# Audio.net
KiCad netlist of a schematic drawn in Altium Designer
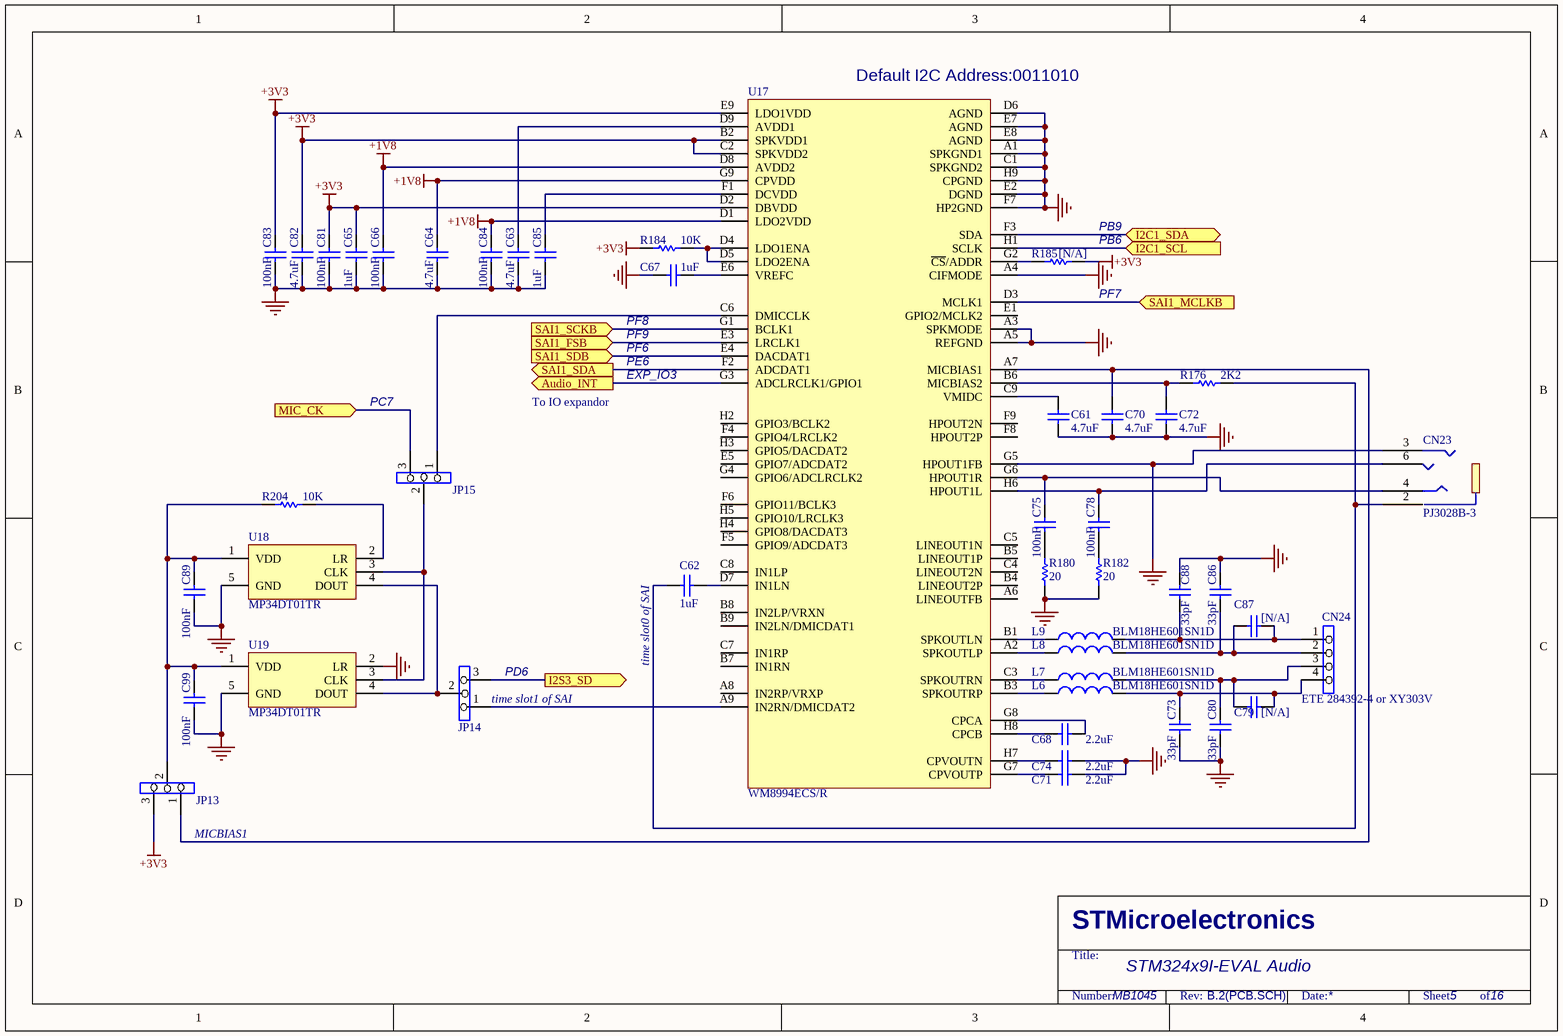
[diagram p0: Audio.SchDoc]

(export (version "E")
  (design (tool "Eeschema 10.0.6"))
  (components
    (comp (ref "C61")
      (value "4.7uF")
      (footprint "0603C")
      (description "Capacitor")
      (fields (field (name "PUBLISHER") "Altium Limited"))
      (libsource (lib "Miscellaneous Devices") (part "Cap"))
    )
    (comp (ref "C62")
      (value "1uF")
      (footprint "0603C")
      (description "Capacitor")
      (fields (field (name "PUBLISHER") "Altium Limited"))
      (libsource (lib "Miscellaneous Devices") (part "CAP"))
    )
    (comp (ref "C63")
      (value "4.7uF")
      (footprint "0603C")
      (description "Capacitor")
      (fields (field (name "PUBLISHER") "Altium Limited"))
      (libsource (lib "Miscellaneous Devices") (part "Cap"))
    )
    (comp (ref "C64")
      (value "4.7uF")
      (footprint "0603C")
      (description "Capacitor")
      (fields (field (name "PUBLISHER") "Altium Limited"))
      (libsource (lib "Miscellaneous Devices") (part "Cap"))
    )
    (comp (ref "C65")
      (value "1uF")
      (footprint "0603C")
      (description "Capacitor")
      (fields (field (name "PUBLISHER") "Altium Limited"))
      (libsource (lib "Miscellaneous Devices") (part "CAP"))
    )
    (comp (ref "C66")
      (value "100nF")
      (footprint "0603C")
      (description "Capacitor")
      (fields (field (name "PUBLISHER") "Altium Limited"))
      (libsource (lib "Miscellaneous Devices") (part "Cap"))
    )
    (comp (ref "C67")
      (value "1uF")
      (footprint "0603C")
      (description "Capacitor")
      (fields (field (name "PUBLISHER") "Altium Limited"))
      (libsource (lib "Miscellaneous Devices") (part "CAP"))
    )
    (comp (ref "C68")
      (value "2.2uF")
      (footprint "0603C")
      (description "Capacitor")
      (fields (field (name "PUBLISHER") "Altium Limited"))
      (libsource (lib "Miscellaneous Devices") (part "CAP"))
    )
    (comp (ref "C70")
      (value "4.7uF")
      (footprint "0603C")
      (description "Capacitor")
      (fields (field (name "PUBLISHER") "Altium Limited"))
      (libsource (lib "Miscellaneous Devices") (part "Cap"))
    )
    (comp (ref "C71")
      (value "2.2uF")
      (footprint "0603C")
      (description "Capacitor")
      (fields (field (name "PUBLISHER") "Altium Limited"))
      (libsource (lib "Miscellaneous Devices") (part "CAP"))
    )
    (comp (ref "C72")
      (value "4.7uF")
      (footprint "0603C")
      (description "Capacitor")
      (fields (field (name "PUBLISHER") "Altium Limited"))
      (libsource (lib "Miscellaneous Devices") (part "Cap"))
    )
    (comp (ref "C73")
      (value "33pF")
      (footprint "0603C")
      (description "Capacitor")
      (fields (field (name "PUBLISHER") "Altium Limited"))
      (libsource (lib "Miscellaneous Devices") (part "Cap"))
    )
    (comp (ref "C74")
      (value "2.2uF")
      (footprint "0603C")
      (description "Capacitor")
      (fields (field (name "PUBLISHER") "Altium Limited"))
      (libsource (lib "Miscellaneous Devices") (part "CAP"))
    )
    (comp (ref "C75")
      (value "100nF")
      (footprint "0603C")
      (description "Capacitor")
      (fields (field (name "PUBLISHER") "Altium Limited"))
      (libsource (lib "Miscellaneous Devices") (part "Cap"))
    )
    (comp (ref "C78")
      (value "100nF")
      (footprint "0603C")
      (description "Capacitor")
      (fields (field (name "PUBLISHER") "Altium Limited"))
      (libsource (lib "Miscellaneous Devices") (part "Cap"))
    )
    (comp (ref "C79")
      (value "[N/A]")
      (footprint "0603C")
      (description "Capacitor")
      (fields (field (name "PUBLISHER") "Altium Limited"))
      (libsource (lib "Miscellaneous Devices") (part "Cap"))
    )
    (comp (ref "C80")
      (value "33pF")
      (footprint "0603C")
      (description "Capacitor")
      (fields (field (name "PUBLISHER") "Altium Limited"))
      (libsource (lib "Miscellaneous Devices") (part "Cap"))
    )
    (comp (ref "C81")
      (value "100nF")
      (footprint "0603C")
      (description "Capacitor")
      (fields (field (name "PUBLISHER") "Altium Limited"))
      (libsource (lib "Miscellaneous Devices") (part "Cap"))
    )
    (comp (ref "C82")
      (value "4.7uF")
      (footprint "0603C")
      (description "Capacitor")
      (fields (field (name "PUBLISHER") "Altium Limited"))
      (libsource (lib "Miscellaneous Devices") (part "Cap"))
    )
    (comp (ref "C83")
      (value "100nF")
      (footprint "0603C")
      (description "Capacitor")
      (fields (field (name "PUBLISHER") "Altium Limited"))
      (libsource (lib "Miscellaneous Devices") (part "Cap"))
    )
    (comp (ref "C84")
      (value "100nF")
      (footprint "0603C")
      (description "Capacitor")
      (fields (field (name "PUBLISHER") "Altium Limited"))
      (libsource (lib "Miscellaneous Devices") (part "Cap"))
    )
    (comp (ref "C85")
      (value "1uF")
      (footprint "0603C")
      (description "Capacitor")
      (fields (field (name "PUBLISHER") "Altium Limited"))
      (libsource (lib "Miscellaneous Devices") (part "CAP"))
    )
    (comp (ref "C86")
      (value "33pF")
      (footprint "0603C")
      (description "Capacitor")
      (fields (field (name "PUBLISHER") "Altium Limited"))
      (libsource (lib "Miscellaneous Devices") (part "Cap"))
    )
    (comp (ref "C87")
      (value "[N/A]")
      (footprint "0603C")
      (description "Capacitor")
      (fields (field (name "PUBLISHER") "Altium Limited"))
      (libsource (lib "Miscellaneous Devices") (part "Cap"))
    )
    (comp (ref "C88")
      (value "33pF")
      (footprint "0603C")
      (description "Capacitor")
      (fields (field (name "PUBLISHER") "Altium Limited"))
      (libsource (lib "Miscellaneous Devices") (part "Cap"))
    )
    (comp (ref "C89")
      (value "100nF")
      (footprint "0603C")
      (description "Capacitor")
      (fields (field (name "PUBLISHER") "Altium Limited"))
      (libsource (lib "Miscellaneous Devices") (part "Cap"))
    )
    (comp (ref "C99")
      (value "100nF")
      (footprint "0603C")
      (description "Capacitor")
      (fields (field (name "PUBLISHER") "Altium Limited"))
      (libsource (lib "Miscellaneous Devices") (part "Cap"))
    )
    (comp (ref "CN23") (value "PJ3028B-3") (footprint "PJ3028B") (libsource (lib "MB786") (part "PJ3028B-3")))
    (comp (ref "CN24")
      (value "ETE 284392-4 or XY303V")
      (footprint "BUCHANAN_284392-4")
      (description "ETE 284392-4")
      (libsource (lib "mb1045") (part "ETE 284392-4 or XY303V"))
    )
    (comp (ref "JP13") (value "~") (footprint "SIP3") (libsource (lib "STR910_SCHLIB") (part "Jumper3")))
    (comp (ref "JP14") (value "~") (footprint "SIP3") (libsource (lib "STR910_SCHLIB") (part "Jumper3")))
    (comp (ref "JP15") (value "~") (footprint "SIP3") (libsource (lib "STR910_SCHLIB") (part "Jumper3")))
    (comp (ref "L6")
      (value "BLM18HE601SN1D")
      (footprint "0603L")
      (description "Inductor")
      (fields (field (name "PUBLISHER") "Altium Limited"))
      (libsource (lib "Miscellaneous Devices") (part "Inductor"))
    )
    (comp (ref "L7")
      (value "BLM18HE601SN1D")
      (footprint "0603L")
      (description "Inductor")
      (fields (field (name "PUBLISHER") "Altium Limited"))
      (libsource (lib "Miscellaneous Devices") (part "Inductor"))
    )
    (comp (ref "L8")
      (value "BLM18HE601SN1D")
      (footprint "0603L")
      (description "Inductor")
      (fields (field (name "PUBLISHER") "Altium Limited"))
      (libsource (lib "Miscellaneous Devices") (part "Inductor"))
    )
    (comp (ref "L9")
      (value "BLM18HE601SN1D")
      (footprint "0603L")
      (description "Inductor")
      (fields (field (name "PUBLISHER") "Altium Limited"))
      (libsource (lib "Miscellaneous Devices") (part "Inductor"))
    )
    (comp (ref "R176")
      (value "2K2")
      (footprint "0603R")
      (description "Resistor")
      (fields (field (name "PUBLISHER") "Altium Limited"))
      (libsource (lib "Miscellaneous Devices") (part "Res1"))
    )
    (comp (ref "R180")
      (value "20")
      (footprint "0603R")
      (description "Resistor")
      (fields (field (name "PUBLISHER") "Altium Limited"))
      (libsource (lib "Miscellaneous Devices") (part "Res1"))
    )
    (comp (ref "R182")
      (value "20")
      (footprint "0603R")
      (description "Resistor")
      (fields (field (name "PUBLISHER") "Altium Limited"))
      (libsource (lib "Miscellaneous Devices") (part "Res1"))
    )
    (comp (ref "R184")
      (value "10K")
      (footprint "0603R")
      (description "Resistor")
      (fields (field (name "PUBLISHER") "Altium Limited"))
      (libsource (lib "Miscellaneous Devices") (part "Res1"))
    )
    (comp (ref "R185")
      (value "[N/A]")
      (footprint "0603R")
      (description "Resistor")
      (fields (field (name "PUBLISHER") "Altium Limited"))
      (libsource (lib "Miscellaneous Devices") (part "Res1"))
    )
    (comp (ref "R204")
      (value "10K")
      (footprint "0603R")
      (description "Resistor")
      (fields (field (name "PUBLISHER") "Altium Limited"))
      (libsource (lib "Miscellaneous Devices") (part "Res1"))
    )
    (comp (ref "U17")
      (value "WM8994ECS/R")
      (footprint "BGA72_0R5_4R5X4")
      (libsource (lib "mb1045") (part "WM8994ECS/R"))
    )
    (comp (ref "U18")
      (value "MP34DT01TR")
      (footprint "MP34DT01TR")
      (description "MEMS audio sensor")
      (fields (field (name "PUBLISHER") "Altium Limited"))
      (libsource (lib "mb1045") (part "MP34DT01TR"))
    )
    (comp (ref "U19")
      (value "MP34DT01TR")
      (footprint "MP34DT01TR")
      (description "MEMS audio sensor")
      (fields (field (name "PUBLISHER") "Altium Limited"))
      (libsource (lib "mb1045") (part "MP34DT01TR"))
    )
  )
  (nets
    (net (code "1") (name "+1V8") (class "Default")
      (node (ref "C64") (pin "1") (pinfunction "1_1") (pintype "passive"))
      (node (ref "C66") (pin "1") (pinfunction "1_1") (pintype "passive"))
      (node (ref "C84") (pin "1") (pinfunction "1_1") (pintype "passive"))
      (node (ref "U17") (pin "D1") (pinfunction "LDO2VDD_D1") (pintype "passive"))
      (node (ref "U17") (pin "D8") (pinfunction "AVDD2_D8") (pintype "passive"))
      (node (ref "U17") (pin "G9") (pinfunction "CPVDD_G9") (pintype "passive"))
    )
    (net (code "2") (name "+3V3") (class "Default")
      (node (ref "C65") (pin "1") (pinfunction "1_1") (pintype "passive"))
      (node (ref "C81") (pin "1") (pinfunction "1_1") (pintype "passive"))
      (node (ref "C82") (pin "1") (pinfunction "1_1") (pintype "passive"))
      (node (ref "C83") (pin "1") (pinfunction "1_1") (pintype "passive"))
      (node (ref "JP13") (pin "3") (pintype "passive"))
      (node (ref "R184") (pin "2") (pinfunction "2_2") (pintype "passive"))
      (node (ref "R185") (pin "1") (pinfunction "1_1") (pintype "passive"))
      (node (ref "U17") (pin "B2") (pinfunction "SPKVDD1_B2") (pintype "passive"))
      (node (ref "U17") (pin "C2") (pinfunction "SPKVDD2_C2") (pintype "passive"))
      (node (ref "U17") (pin "D2") (pinfunction "DBVDD_D2") (pintype "passive"))
      (node (ref "U17") (pin "E9") (pinfunction "LDO1VDD_E9") (pintype "passive"))
    )
    (net (code "3") (name "/Audio_INT") (class "Default")
      (node (ref "U17") (pin "G3") (pinfunction "ADCLRCLK1/GPIO1_G3") (pintype "passive"))
    )
    (net (code "4") (name "/I2C1_SCL") (class "Default")
      (node (ref "U17") (pin "H1") (pinfunction "SCLK_H1") (pintype "passive"))
    )
    (net (code "5") (name "/I2C1_SDA") (class "Default")
      (node (ref "U17") (pin "F3") (pinfunction "SDA_F3") (pintype "passive"))
    )
    (net (code "6") (name "/I2S3_SD") (class "Default") (node (ref "JP14") (pin "3") (pintype "passive")))
    (net (code "7") (name "/MIC_CK") (class "Default") (node (ref "JP15") (pin "3") (pintype "passive")))
    (net (code "8") (name "/SAI1_FSB") (class "Default")
      (node (ref "U17") (pin "E3") (pinfunction "LRCLK1_E3") (pintype "passive"))
    )
    (net (code "9") (name "/SAI1_MCLKB") (class "Default")
      (node (ref "U17") (pin "D3") (pinfunction "MCLK1_D3") (pintype "passive"))
    )
    (net (code "10") (name "/SAI1_SCKB") (class "Default")
      (node (ref "U17") (pin "G1") (pinfunction "BCLK1_G1") (pintype "passive"))
    )
    (net (code "11") (name "/SAI1_SDA") (class "Default")
      (node (ref "U17") (pin "F2") (pinfunction "ADCDAT1_F2") (pintype "passive"))
    )
    (net (code "12") (name "/SAI1_SDB") (class "Default")
      (node (ref "U17") (pin "E4") (pinfunction "DACDAT1_E4") (pintype "passive"))
    )
    (net (code "13") (name "GND") (class "Default")
      (node (ref "C61") (pin "1") (pinfunction "1_1") (pintype "passive"))
      (node (ref "C63") (pin "2") (pinfunction "2_2") (pintype "passive"))
      (node (ref "C64") (pin "2") (pinfunction "2_2") (pintype "passive"))
      (node (ref "C65") (pin "2") (pinfunction "2_2") (pintype "passive"))
      (node (ref "C66") (pin "2") (pinfunction "2_2") (pintype "passive"))
      (node (ref "C67") (pin "2") (pinfunction "2_2") (pintype "passive"))
      (node (ref "C70") (pin "1") (pinfunction "1_1") (pintype "passive"))
      (node (ref "C71") (pin "2") (pinfunction "2_2") (pintype "passive"))
      (node (ref "C72") (pin "1") (pinfunction "1_1") (pintype "passive"))
      (node (ref "C73") (pin "2") (pinfunction "2_2") (pintype "passive"))
      (node (ref "C74") (pin "2") (pinfunction "2_2") (pintype "passive"))
      (node (ref "C80") (pin "2") (pinfunction "2_2") (pintype "passive"))
      (node (ref "C81") (pin "2") (pinfunction "2_2") (pintype "passive"))
      (node (ref "C82") (pin "2") (pinfunction "2_2") (pintype "passive"))
      (node (ref "C83") (pin "2") (pinfunction "2_2") (pintype "passive"))
      (node (ref "C84") (pin "2") (pinfunction "2_2") (pintype "passive"))
      (node (ref "C85") (pin "2") (pinfunction "2_2") (pintype "passive"))
      (node (ref "C86") (pin "1") (pinfunction "1_1") (pintype "passive"))
      (node (ref "C88") (pin "1") (pinfunction "1_1") (pintype "passive"))
      (node (ref "C89") (pin "2") (pinfunction "2_2") (pintype "passive"))
      (node (ref "C99") (pin "2") (pinfunction "2_2") (pintype "passive"))
      (node (ref "CN23") (pin "3") (pintype "passive"))
      (node (ref "R180") (pin "2") (pinfunction "2_2") (pintype "passive"))
      (node (ref "R182") (pin "2") (pinfunction "2_2") (pintype "passive"))
      (node (ref "U17") (pin "A1") (pinfunction "SPKGND1_A1") (pintype "passive"))
      (node (ref "U17") (pin "A3") (pinfunction "SPKMODE_A3") (pintype "passive"))
      (node (ref "U17") (pin "A4") (pinfunction "CIFMODE_A4") (pintype "passive"))
      (node (ref "U17") (pin "A5") (pinfunction "REFGND_A5") (pintype "passive"))
      (node (ref "U17") (pin "C1") (pinfunction "SPKGND2_C1") (pintype "passive"))
      (node (ref "U17") (pin "D6") (pinfunction "AGND_D6") (pintype "passive"))
      (node (ref "U17") (pin "E2") (pinfunction "DGND_E2") (pintype "passive"))
      (node (ref "U17") (pin "E7") (pinfunction "AGND_E7") (pintype "passive"))
      (node (ref "U17") (pin "E8") (pinfunction "AGND_E8") (pintype "passive"))
      (node (ref "U17") (pin "F7") (pinfunction "HP2GND_F7") (pintype "passive"))
      (node (ref "U17") (pin "G5") (pinfunction "HPOUT1FB_G5") (pintype "passive"))
      (node (ref "U17") (pin "H9") (pinfunction "CPGND_H9") (pintype "passive"))
      (node (ref "U18") (pin "5") (pinfunction "GND_5") (pintype "passive"))
      (node (ref "U19") (pin "2") (pinfunction "LR_2") (pintype "passive"))
      (node (ref "U19") (pin "5") (pinfunction "GND_5") (pintype "passive"))
    )
    (net (code "14") (name "Net-(C62-Pad2)") (class "Default")
      (node (ref "C62") (pin "2") (pinfunction "2_2") (pintype "passive"))
      (node (ref "CN23") (pin "2") (pintype "passive"))
      (node (ref "R176") (pin "1") (pinfunction "1_1") (pintype "passive"))
    )
    (net (code "15") (name "Net-(C73-Pad1)") (class "Default")
      (node (ref "C73") (pin "1") (pinfunction "1_1") (pintype "passive"))
      (node (ref "C79") (pin "2") (pinfunction "2_2") (pintype "passive"))
      (node (ref "CN24") (pin "4") (pintype "passive"))
      (node (ref "L6") (pin "2") (pinfunction "2_2") (pintype "passive"))
    )
    (net (code "16") (name "Net-(C75-Pad2)") (class "Default")
      (node (ref "C75") (pin "2") (pinfunction "2_2") (pintype "passive"))
      (node (ref "R180") (pin "1") (pinfunction "1_1") (pintype "passive"))
    )
    (net (code "17") (name "Net-(C78-Pad2)") (class "Default")
      (node (ref "C78") (pin "2") (pinfunction "2_2") (pintype "passive"))
      (node (ref "R182") (pin "1") (pinfunction "1_1") (pintype "passive"))
    )
    (net (code "18") (name "Net-(C79-Pad1)") (class "Default")
      (node (ref "C79") (pin "1") (pinfunction "1_1") (pintype "passive"))
      (node (ref "C80") (pin "1") (pinfunction "1_1") (pintype "passive"))
      (node (ref "CN24") (pin "3") (pintype "passive"))
      (node (ref "L7") (pin "2") (pinfunction "2_2") (pintype "passive"))
    )
    (net (code "19") (name "Net-(C86-Pad2)") (class "Default")
      (node (ref "C86") (pin "2") (pinfunction "2_2") (pintype "passive"))
      (node (ref "C87") (pin "1") (pinfunction "1_1") (pintype "passive"))
      (node (ref "CN24") (pin "2") (pintype "passive"))
      (node (ref "L8") (pin "2") (pinfunction "2_2") (pintype "passive"))
    )
    (net (code "20") (name "Net-(C87-Pad2)") (class "Default")
      (node (ref "C87") (pin "2") (pinfunction "2_2") (pintype "passive"))
      (node (ref "C88") (pin "2") (pinfunction "2_2") (pintype "passive"))
      (node (ref "CN24") (pin "1") (pintype "passive"))
      (node (ref "L9") (pin "2") (pinfunction "2_2") (pintype "passive"))
    )
    (net (code "21") (name "Net-(U17-AVDD1)") (class "Default")
      (node (ref "C63") (pin "1") (pinfunction "1_1") (pintype "passive"))
      (node (ref "U17") (pin "D9") (pinfunction "AVDD1_D9") (pintype "passive"))
    )
    (net (code "22") (name "Net-(U17-CPCA)") (class "Default")
      (node (ref "C68") (pin "2") (pinfunction "2_2") (pintype "passive"))
      (node (ref "U17") (pin "G8") (pinfunction "CPCA_G8") (pintype "passive"))
    )
    (net (code "23") (name "Net-(U17-CPCB)") (class "Default")
      (node (ref "C68") (pin "1") (pinfunction "1_1") (pintype "passive"))
      (node (ref "U17") (pin "H8") (pinfunction "CPCB_H8") (pintype "passive"))
    )
    (net (code "24") (name "Net-(U17-CPVOUTN)") (class "Default")
      (node (ref "C74") (pin "1") (pinfunction "1_1") (pintype "passive"))
      (node (ref "U17") (pin "H7") (pinfunction "CPVOUTN_H7") (pintype "passive"))
    )
    (net (code "25") (name "Net-(U17-CPVOUTP)") (class "Default")
      (node (ref "C71") (pin "1") (pinfunction "1_1") (pintype "passive"))
      (node (ref "U17") (pin "G7") (pinfunction "CPVOUTP_G7") (pintype "passive"))
    )
    (net (code "26") (name "Net-(U17-DCVDD)") (class "Default")
      (node (ref "C85") (pin "1") (pinfunction "1_1") (pintype "passive"))
      (node (ref "U17") (pin "F1") (pinfunction "DCVDD_F1") (pintype "passive"))
    )
    (net (code "27") (name "Net-(U17-DMICCLK)") (class "Default")
      (node (ref "JP15") (pin "1") (pintype "passive"))
      (node (ref "U17") (pin "C6") (pinfunction "DMICCLK_C6") (pintype "passive"))
    )
    (net (code "28") (name "Net-(U17-HPOUT1L)") (class "Default")
      (node (ref "C78") (pin "1") (pinfunction "1_1") (pintype "passive"))
      (node (ref "CN23") (pin "6") (pintype "passive"))
      (node (ref "U17") (pin "H6") (pinfunction "HPOUT1L_H6") (pintype "passive"))
    )
    (net (code "29") (name "Net-(U17-HPOUT1R)") (class "Default")
      (node (ref "C75") (pin "1") (pinfunction "1_1") (pintype "passive"))
      (node (ref "CN23") (pin "4") (pintype "passive"))
      (node (ref "U17") (pin "G6") (pinfunction "HPOUT1R_G6") (pintype "passive"))
    )
    (net (code "30") (name "Net-(U17-IN1LN)") (class "Default")
      (node (ref "C62") (pin "1") (pinfunction "1_1") (pintype "passive"))
      (node (ref "U17") (pin "D7") (pinfunction "IN1LN_D7") (pintype "passive"))
    )
    (net (code "31") (name "Net-(U17-IN2RN{slash}DMICDAT2)") (class "Default")
      (node (ref "JP14") (pin "1") (pintype "passive"))
      (node (ref "U17") (pin "A9") (pinfunction "IN2RN/DMICDAT2_A9") (pintype "passive"))
    )
    (net (code "32") (name "Net-(U17-LDO1ENA)") (class "Default")
      (node (ref "R184") (pin "1") (pinfunction "1_1") (pintype "passive"))
      (node (ref "U17") (pin "D4") (pinfunction "LDO1ENA_D4") (pintype "passive"))
      (node (ref "U17") (pin "D5") (pinfunction "LDO2ENA_D5") (pintype "passive"))
    )
    (net (code "33") (name "Net-(U17-MICBIAS1)") (class "Default")
      (node (ref "C70") (pin "2") (pinfunction "2_2") (pintype "passive"))
      (node (ref "JP13") (pin "1") (pintype "passive"))
      (node (ref "U17") (pin "A7") (pinfunction "MICBIAS1_A7") (pintype "passive"))
    )
    (net (code "34") (name "Net-(U17-MICBIAS2)") (class "Default")
      (node (ref "C72") (pin "2") (pinfunction "2_2") (pintype "passive"))
      (node (ref "R176") (pin "2") (pinfunction "2_2") (pintype "passive"))
      (node (ref "U17") (pin "B6") (pinfunction "MICBIAS2_B6") (pintype "passive"))
    )
    (net (code "35") (name "Net-(U17-SPKOUTLN)") (class "Default")
      (node (ref "L9") (pin "1") (pinfunction "1_1") (pintype "passive"))
      (node (ref "U17") (pin "B1") (pinfunction "SPKOUTLN_B1") (pintype "passive"))
    )
    (net (code "36") (name "Net-(U17-SPKOUTLP)") (class "Default")
      (node (ref "L8") (pin "1") (pinfunction "1_1") (pintype "passive"))
      (node (ref "U17") (pin "A2") (pinfunction "SPKOUTLP_A2") (pintype "passive"))
    )
    (net (code "37") (name "Net-(U17-SPKOUTRN)") (class "Default")
      (node (ref "L7") (pin "1") (pinfunction "1_1") (pintype "passive"))
      (node (ref "U17") (pin "C3") (pinfunction "SPKOUTRN_C3") (pintype "passive"))
    )
    (net (code "38") (name "Net-(U17-SPKOUTRP)") (class "Default")
      (node (ref "L6") (pin "1") (pinfunction "1_1") (pintype "passive"))
      (node (ref "U17") (pin "B3") (pinfunction "SPKOUTRP_B3") (pintype "passive"))
    )
    (net (code "39") (name "Net-(U17-VMIDC)") (class "Default")
      (node (ref "C61") (pin "2") (pinfunction "2_2") (pintype "passive"))
      (node (ref "U17") (pin "C9") (pinfunction "VMIDC_C9") (pintype "passive"))
    )
    (net (code "40") (name "Net-(U17-VREFC)") (class "Default")
      (node (ref "C67") (pin "1") (pinfunction "1_1") (pintype "passive"))
      (node (ref "U17") (pin "E6") (pinfunction "VREFC_E6") (pintype "passive"))
    )
    (net (code "41") (name "Net-(U17-~{CS}{slash}ADDR)") (class "Default")
      (node (ref "R185") (pin "2") (pinfunction "2_2") (pintype "passive"))
      (node (ref "U17") (pin "G2") (pinfunction "~{CS}/ADDR_G2") (pintype "passive"))
    )
    (net (code "42") (name "Net-(U18-CLK)") (class "Default")
      (node (ref "JP15") (pin "2") (pintype "passive"))
      (node (ref "U18") (pin "3") (pinfunction "CLK_3") (pintype "passive"))
      (node (ref "U19") (pin "3") (pinfunction "CLK_3") (pintype "passive"))
    )
    (net (code "43") (name "Net-(U18-DOUT)") (class "Default")
      (node (ref "JP14") (pin "2") (pintype "passive"))
      (node (ref "U18") (pin "4") (pinfunction "DOUT_4") (pintype "passive"))
      (node (ref "U19") (pin "4") (pinfunction "DOUT_4") (pintype "passive"))
    )
    (net (code "44") (name "Net-(U18-LR)") (class "Default")
      (node (ref "R204") (pin "1") (pinfunction "1_1") (pintype "passive"))
      (node (ref "U18") (pin "2") (pinfunction "LR_2") (pintype "passive"))
    )
    (net (code "45") (name "Net-(U18-VDD)") (class "Default")
      (node (ref "C89") (pin "1") (pinfunction "1_1") (pintype "passive"))
      (node (ref "C99") (pin "1") (pinfunction "1_1") (pintype "passive"))
      (node (ref "JP13") (pin "2") (pintype "passive"))
      (node (ref "R204") (pin "2") (pinfunction "2_2") (pintype "passive"))
      (node (ref "U18") (pin "1") (pinfunction "VDD_1") (pintype "passive"))
      (node (ref "U19") (pin "1") (pinfunction "VDD_1") (pintype "passive"))
    )
    (net (code "46") (name "unconnected-(U17-GPIO2{slash}MCLK2-PadE1)") (class "Default")
      (node (ref "U17") (pin "E1") (pinfunction "GPIO2/MCLK2_E1") (pintype "passive"))
    )
    (net (code "47") (name "unconnected-(U17-GPIO3{slash}BCLK2-PadH2)") (class "Default")
      (node (ref "U17") (pin "H2") (pinfunction "GPIO3/BCLK2_H2") (pintype "passive"))
    )
    (net (code "48") (name "unconnected-(U17-GPIO4{slash}LRCLK2-PadF4)") (class "Default")
      (node (ref "U17") (pin "F4") (pinfunction "GPIO4/LRCLK2_F4") (pintype "passive"))
    )
    (net (code "49") (name "unconnected-(U17-GPIO5{slash}DACDAT2-PadH3)") (class "Default")
      (node (ref "U17") (pin "H3") (pinfunction "GPIO5/DACDAT2_H3") (pintype "passive"))
    )
    (net (code "50") (name "unconnected-(U17-GPIO6{slash}ADCLRCLK2-PadG4)") (class "Default")
      (node (ref "U17") (pin "G4") (pinfunction "GPIO6/ADCLRCLK2_G4") (pintype "passive"))
    )
    (net (code "51") (name "unconnected-(U17-GPIO7{slash}ADCDAT2-PadE5)") (class "Default")
      (node (ref "U17") (pin "E5") (pinfunction "GPIO7/ADCDAT2_E5") (pintype "passive"))
    )
    (net (code "52") (name "unconnected-(U17-GPIO8{slash}DACDAT3-PadH4)") (class "Default")
      (node (ref "U17") (pin "H4") (pinfunction "GPIO8/DACDAT3_H4") (pintype "passive"))
    )
    (net (code "53") (name "unconnected-(U17-GPIO9{slash}ADCDAT3-PadF5)") (class "Default")
      (node (ref "U17") (pin "F5") (pinfunction "GPIO9/ADCDAT3_F5") (pintype "passive"))
    )
    (net (code "54") (name "unconnected-(U17-GPIO10{slash}LRCLK3-PadH5)") (class "Default")
      (node (ref "U17") (pin "H5") (pinfunction "GPIO10/LRCLK3_H5") (pintype "passive"))
    )
    (net (code "55") (name "unconnected-(U17-GPIO11{slash}BCLK3-PadF6)") (class "Default")
      (node (ref "U17") (pin "F6") (pinfunction "GPIO11/BCLK3_F6") (pintype "passive"))
    )
    (net (code "56") (name "unconnected-(U17-HPOUT2N-PadF9)") (class "Default")
      (node (ref "U17") (pin "F9") (pinfunction "HPOUT2N_F9") (pintype "passive"))
    )
    (net (code "57") (name "unconnected-(U17-HPOUT2P-PadF8)") (class "Default")
      (node (ref "U17") (pin "F8") (pinfunction "HPOUT2P_F8") (pintype "passive"))
    )
    (net (code "58") (name "unconnected-(U17-IN1LP-PadC8)") (class "Default")
      (node (ref "U17") (pin "C8") (pinfunction "IN1LP_C8") (pintype "passive"))
    )
    (net (code "59") (name "unconnected-(U17-IN1RN-PadB7)") (class "Default")
      (node (ref "U17") (pin "B7") (pinfunction "IN1RN_B7") (pintype "passive"))
    )
    (net (code "60") (name "unconnected-(U17-IN1RP-PadC7)") (class "Default")
      (node (ref "U17") (pin "C7") (pinfunction "IN1RP_C7") (pintype "passive"))
    )
    (net (code "61") (name "unconnected-(U17-IN2LN{slash}DMICDAT1-PadB9)") (class "Default")
      (node (ref "U17") (pin "B9") (pinfunction "IN2LN/DMICDAT1_B9") (pintype "passive"))
    )
    (net (code "62") (name "unconnected-(U17-IN2LP{slash}VRXN-PadB8)") (class "Default")
      (node (ref "U17") (pin "B8") (pinfunction "IN2LP/VRXN_B8") (pintype "passive"))
    )
    (net (code "63") (name "unconnected-(U17-IN2RP{slash}VRXP-PadA8)") (class "Default")
      (node (ref "U17") (pin "A8") (pinfunction "IN2RP/VRXP_A8") (pintype "passive"))
    )
    (net (code "64") (name "unconnected-(U17-LINEOUT1N-PadC5)") (class "Default")
      (node (ref "U17") (pin "C5") (pinfunction "LINEOUT1N_C5") (pintype "passive"))
    )
    (net (code "65") (name "unconnected-(U17-LINEOUT1P-PadB5)") (class "Default")
      (node (ref "U17") (pin "B5") (pinfunction "LINEOUT1P_B5") (pintype "passive"))
    )
    (net (code "66") (name "unconnected-(U17-LINEOUT2N-PadC4)") (class "Default")
      (node (ref "U17") (pin "C4") (pinfunction "LINEOUT2N_C4") (pintype "passive"))
    )
    (net (code "67") (name "unconnected-(U17-LINEOUT2P-PadB4)") (class "Default")
      (node (ref "U17") (pin "B4") (pinfunction "LINEOUT2P_B4") (pintype "passive"))
    )
    (net (code "68") (name "unconnected-(U17-LINEOUTFB-PadA6)") (class "Default")
      (node (ref "U17") (pin "A6") (pinfunction "LINEOUTFB_A6") (pintype "passive"))
    )
  )
)
